# USB.net
KiCad netlist of a schematic drawn in Altium Designer
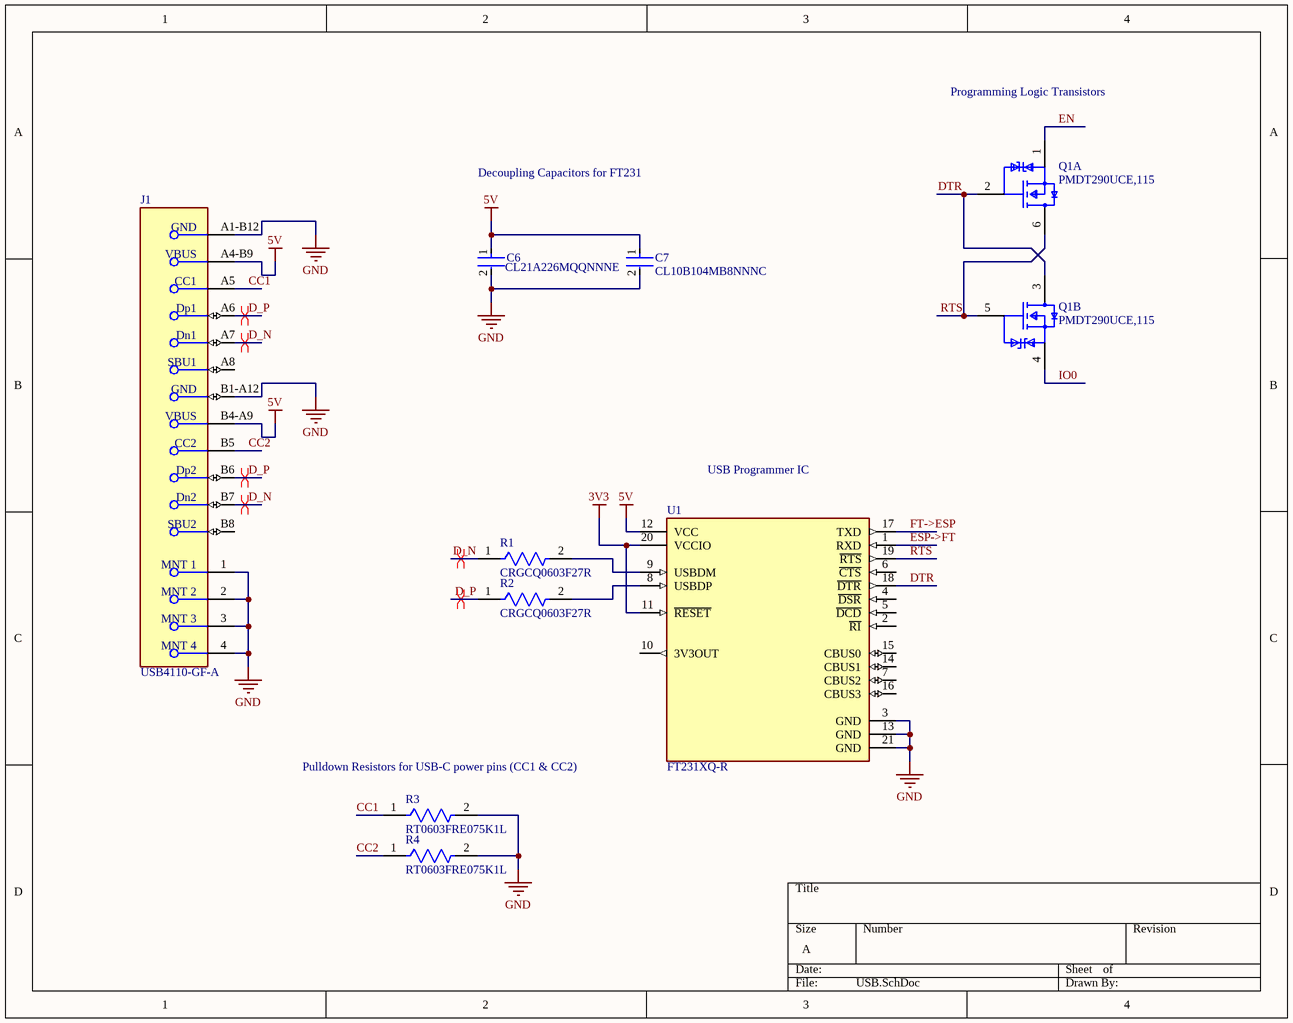
[diagram p0: USB.SchDoc]

(export (version "E")
  (design (tool "Eeschema 10.0.6"))
  (components
    (comp (ref "C6")
      (value "CL21A226MQQNNNE")
      (footprint "FP-CL21-IPC_A")
      (description "CL21 Series 0805 22uF 6.3V ±20% Tolerance X5R Multilayer Ceramic Chip Capacitor")
      (fields (field (name "TOLERANCE") "20%"))
      (libsource (lib "Altium Content Vault") (part "b4654b650e69147ec39a6b967a45e02"))
    )
    (comp (ref "C7")
      (value "CL10B104MB8NNNC")
      (footprint "FP-CL10-IPC_C")
      (description "Cap Ceramic 100nF 50V X7R ±20% Pad SMD 0603 +125°C T/R")
      (fields (field (name "TOLERANCE") "20%"))
      (libsource (lib "Altium Content Vault") (part "b4654b650e69147ec39a6b967a45e02"))
    )
    (comp (ref "J1")
      (value "USB4110-GF-A")
      (footprint "FP-USB4110-GF-A-MFG")
      (description "CONN USB 2.0 TYPE-C R/A SMT")
      (fields
        (field (name "OCTOPART") "https://octopart.com/usb4110-gf-a-gct-103941985")
        (field (name "MANUFACTURER") "GCT")
      )
      (libsource (lib "Altium Content Vault") (part "e23f2b38bb3c3f98e683ebab9ede730"))
    )
    (comp (ref "Q1")
      (value "PMDT290UCE,115")
      (footprint "FP-SOT666-MFG")
      (description "MOSFET N/P-CH 20V SOT666")
      (libsource (lib "Altium Content Vault") (part "082a9c01902c4f1c4be92f72fc0e922"))
    )
    (comp (ref "R1")
      (value "CRGCQ0603F27R")
      (footprint "FP-CRGCQ0603-IPC_C")
      (description "CRGCQ 0603 27R 1%")
      (fields
        (field (name "MANUFACTURER") "TE Connectivity")
        (field (name "OCTOPART") "https://octopart.com/crgcq0603f27r-te+connectivity-91018062")
      )
      (libsource (lib "Altium Content Vault") (part "1029c3af85768c4190bb7ad29bc67b5"))
    )
    (comp (ref "R2")
      (value "CRGCQ0603F27R")
      (footprint "FP-CRGCQ0603-IPC_C")
      (description "CRGCQ 0603 27R 1%")
      (fields
        (field (name "MANUFACTURER") "TE Connectivity")
        (field (name "OCTOPART") "https://octopart.com/crgcq0603f27r-te+connectivity-91018062")
      )
      (libsource (lib "Altium Content Vault") (part "1029c3af85768c4190bb7ad29bc67b5"))
    )
    (comp (ref "R3")
      (value "RT0603FRE075K1L")
      (footprint "FP-RT0603-MFG")
      (description "RES SMD 5.1K OHM 1% 1/10W 0603")
      (fields
        (field (name "MANUFACTURER") "Yageo")
        (field (name "OCTOPART") "https://octopart.com/rt0603fre075k1l-yageo-1421390")
      )
      (libsource (lib "Altium Content Vault") (part "1029c3af85768c4190bb7ad29bc67b5"))
    )
    (comp (ref "R4")
      (value "RT0603FRE075K1L")
      (footprint "FP-RT0603-MFG")
      (description "RES SMD 5.1K OHM 1% 1/10W 0603")
      (fields
        (field (name "MANUFACTURER") "Yageo")
        (field (name "OCTOPART") "https://octopart.com/rt0603fre075k1l-yageo-1421390")
      )
      (libsource (lib "Altium Content Vault") (part "1029c3af85768c4190bb7ad29bc67b5"))
    )
    (comp (ref "U1")
      (value "FT231XQ-R")
      (footprint "FP-QFN-20-MFG")
      (description "IC USB SERIAL FULL UART 20QFN")
      (libsource (lib "Altium Content Vault") (part "1a58eaec777a01ae16a7011961d8d4e"))
    )
  )
  (nets
    (net (code "1") (name "/CC1") (class "Default")
      (node (ref "J1") (pin "A5") (pinfunction "CC1_A5") (pintype "power_in"))
      (node (ref "R3") (pin "1") (pinfunction "1_1") (pintype "passive"))
    )
    (net (code "2") (name "/CC2") (class "Default")
      (node (ref "J1") (pin "B5") (pinfunction "CC2_B5") (pintype "power_in"))
      (node (ref "R4") (pin "1") (pinfunction "1_1") (pintype "passive"))
    )
    (net (code "3") (name "/DTR") (class "Default")
      (node (ref "Q1") (pin "2") (pinfunction "G1_2") (pintype "passive"))
      (node (ref "Q1") (pin "3") (pinfunction "D2_3") (pintype "passive"))
      (node (ref "U1") (pin "18") (pinfunction "~{DTR}_18") (pintype "output"))
    )
    (net (code "4") (name "/D_N") (class "Default")
      (node (ref "J1") (pin "A7") (pinfunction "Dn1_A7") (pintype "bidirectional"))
      (node (ref "J1") (pin "B7") (pinfunction "Dn2_B7") (pintype "bidirectional"))
      (node (ref "R1") (pin "1") (pinfunction "1_1") (pintype "passive"))
    )
    (net (code "5") (name "/D_P") (class "Default")
      (node (ref "J1") (pin "A6") (pinfunction "Dp1_A6") (pintype "bidirectional"))
      (node (ref "J1") (pin "B6") (pinfunction "Dp2_B6") (pintype "bidirectional"))
      (node (ref "R2") (pin "1") (pinfunction "1_1") (pintype "passive"))
    )
    (net (code "6") (name "/EN") (class "Default")
      (node (ref "Q1") (pin "1") (pinfunction "S1_1") (pintype "passive"))
    )
    (net (code "7") (name "/ESP->FT") (class "Default")
      (node (ref "U1") (pin "1") (pinfunction "RXD_1") (pintype "input"))
    )
    (net (code "8") (name "/FT->ESP") (class "Default")
      (node (ref "U1") (pin "17") (pinfunction "TXD_17") (pintype "output"))
    )
    (net (code "9") (name "/IO0") (class "Default")
      (node (ref "Q1") (pin "4") (pinfunction "S2_4") (pintype "passive"))
    )
    (net (code "10") (name "/RTS") (class "Default")
      (node (ref "Q1") (pin "5") (pinfunction "G2_5") (pintype "passive"))
      (node (ref "Q1") (pin "6") (pinfunction "D1_6") (pintype "passive"))
      (node (ref "U1") (pin "19") (pinfunction "~{RTS}_19") (pintype "output"))
    )
    (net (code "11") (name "3V3") (class "Default")
      (node (ref "U1") (pin "11") (pinfunction "~{RESET}_11") (pintype "input"))
      (node (ref "U1") (pin "20") (pinfunction "VCCIO_20") (pintype "power_in"))
    )
    (net (code "12") (name "5V") (class "Default")
      (node (ref "C6") (pin "1") (pinfunction "1_1") (pintype "passive"))
      (node (ref "C7") (pin "1") (pinfunction "1_1") (pintype "passive"))
      (node (ref "J1") (pin "A4-B9") (pinfunction "VBUS_A4-B9") (pintype "power_in"))
      (node (ref "J1") (pin "B4-A9") (pinfunction "VBUS_B4-A9") (pintype "power_in"))
      (node (ref "U1") (pin "12") (pinfunction "VCC_12") (pintype "power_in"))
    )
    (net (code "13") (name "GND") (class "Default")
      (node (ref "C6") (pin "2") (pinfunction "2_2") (pintype "passive"))
      (node (ref "C7") (pin "2") (pinfunction "2_2") (pintype "passive"))
      (node (ref "J1") (pin "1") (pinfunction "MNT_1_1") (pintype "passive"))
      (node (ref "J1") (pin "2") (pinfunction "MNT_2_2") (pintype "passive"))
      (node (ref "J1") (pin "3") (pinfunction "MNT_3_3") (pintype "passive"))
      (node (ref "J1") (pin "4") (pinfunction "MNT_4_4") (pintype "passive"))
      (node (ref "J1") (pin "A1-B12") (pinfunction "GND_A1-B12") (pintype "passive"))
      (node (ref "J1") (pin "B1-A12") (pinfunction "GND_B1-A12") (pintype "bidirectional"))
      (node (ref "R3") (pin "2") (pinfunction "2_2") (pintype "passive"))
      (node (ref "R4") (pin "2") (pinfunction "2_2") (pintype "passive"))
      (node (ref "U1") (pin "13") (pinfunction "GND_13") (pintype "open_emitter"))
      (node (ref "U1") (pin "21") (pinfunction "GND_21") (pintype "power_in"))
      (node (ref "U1") (pin "3") (pinfunction "GND_3") (pintype "power_in"))
    )
    (net (code "14") (name "Net-(U1-USBDM)") (class "Default")
      (node (ref "R1") (pin "2") (pinfunction "2_2") (pintype "passive"))
      (node (ref "U1") (pin "9") (pinfunction "USBDM_9") (pintype "input"))
    )
    (net (code "15") (name "Net-(U1-USBDP)") (class "Default")
      (node (ref "R2") (pin "2") (pinfunction "2_2") (pintype "passive"))
      (node (ref "U1") (pin "8") (pinfunction "USBDP_8") (pintype "input"))
    )
    (net (code "16") (name "unconnected-(J1-SBU1-PadA8)") (class "Default")
      (node (ref "J1") (pin "A8") (pinfunction "SBU1_A8") (pintype "bidirectional"))
    )
    (net (code "17") (name "unconnected-(J1-SBU2-PadB8)") (class "Default")
      (node (ref "J1") (pin "B8") (pinfunction "SBU2_B8") (pintype "bidirectional"))
    )
    (net (code "18") (name "unconnected-(U1-3V3OUT-Pad10)") (class "Default")
      (node (ref "U1") (pin "10") (pinfunction "3V3OUT_10") (pintype "output"))
    )
    (net (code "19") (name "unconnected-(U1-CBUS0-Pad15)") (class "Default")
      (node (ref "U1") (pin "15") (pinfunction "CBUS0_15") (pintype "bidirectional"))
    )
    (net (code "20") (name "unconnected-(U1-CBUS1-Pad14)") (class "Default")
      (node (ref "U1") (pin "14") (pinfunction "CBUS1_14") (pintype "bidirectional"))
    )
    (net (code "21") (name "unconnected-(U1-CBUS2-Pad7)") (class "Default")
      (node (ref "U1") (pin "7") (pinfunction "CBUS2_7") (pintype "bidirectional"))
    )
    (net (code "22") (name "unconnected-(U1-CBUS3-Pad16)") (class "Default")
      (node (ref "U1") (pin "16") (pinfunction "CBUS3_16") (pintype "bidirectional"))
    )
    (net (code "23") (name "unconnected-(U1-~{CTS}-Pad6)") (class "Default")
      (node (ref "U1") (pin "6") (pinfunction "~{CTS}_6") (pintype "input"))
    )
    (net (code "24") (name "unconnected-(U1-~{DCD}-Pad5)") (class "Default")
      (node (ref "U1") (pin "5") (pinfunction "~{DCD}_5") (pintype "input"))
    )
    (net (code "25") (name "unconnected-(U1-~{DSR}-Pad4)") (class "Default")
      (node (ref "U1") (pin "4") (pinfunction "~{DSR}_4") (pintype "input"))
    )
    (net (code "26") (name "unconnected-(U1-~{RI}-Pad2)") (class "Default")
      (node (ref "U1") (pin "2") (pinfunction "~{RI}_2") (pintype "input"))
    )
  )
)
